# 05_RS232_USB.net
KiCad netlist of a schematic drawn in Altium Designer
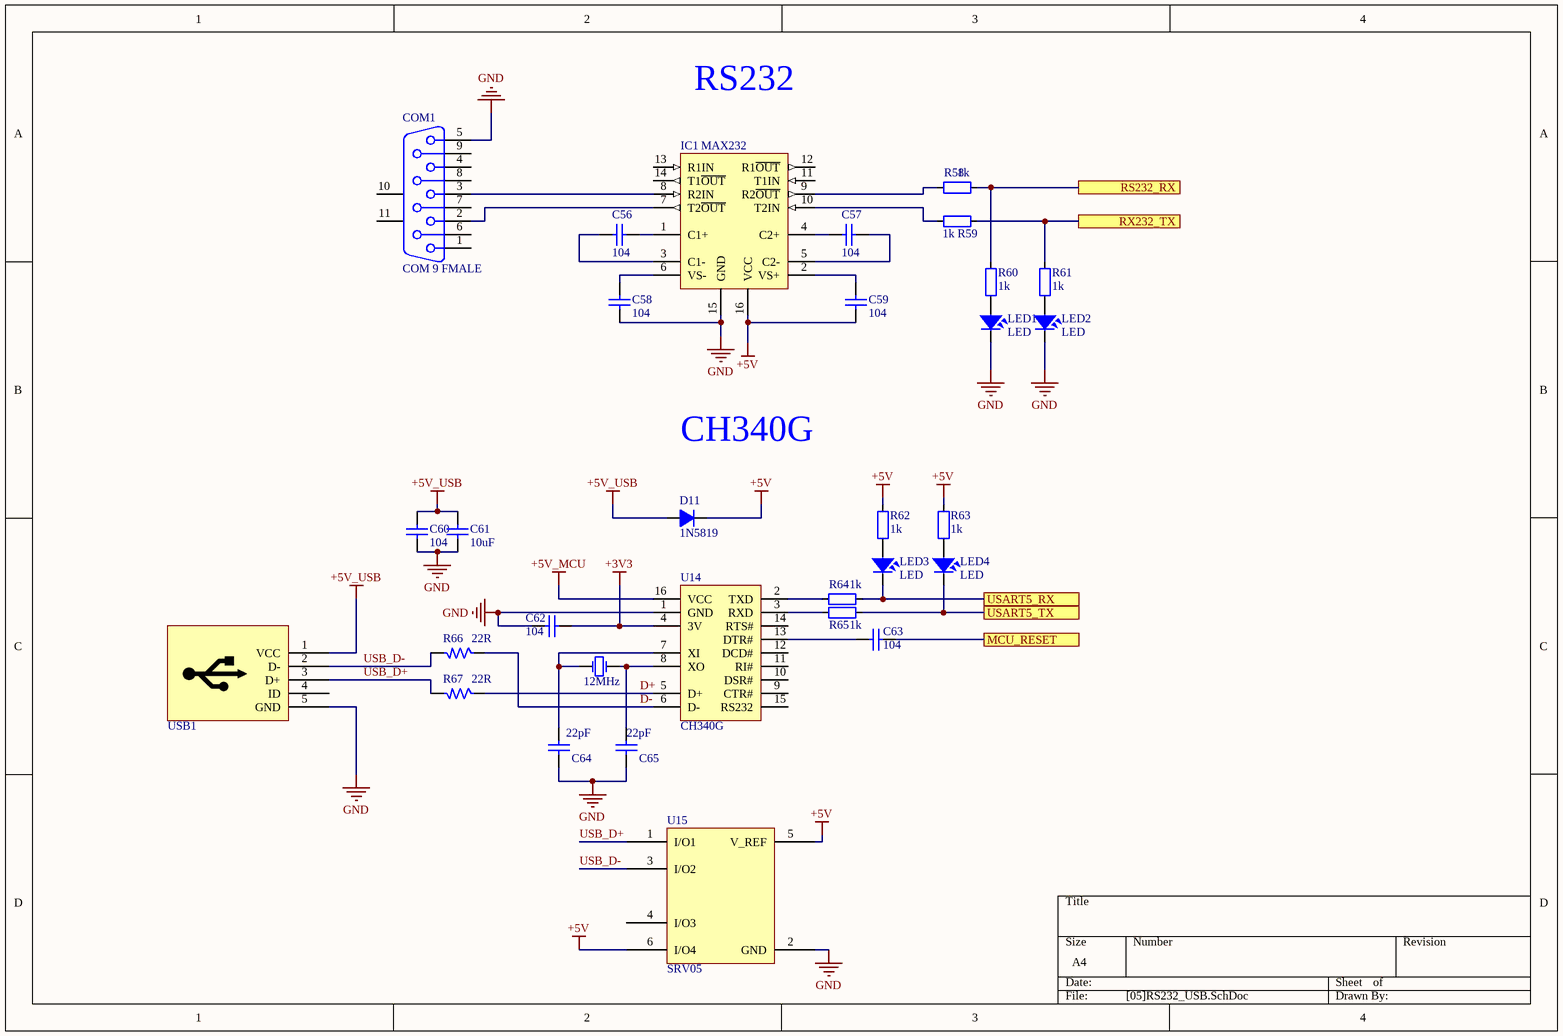
[diagram p0: [05]RS232_USB.SchDoc]

(export (version "E")
  (design (tool "Eeschema 10.0.6"))
  (components
    (comp (ref "C56")
      (value "104")
      (footprint "CAP_0603")
      (description "Capacitor")
      (fields (field (name "PUBLISHER") "Altium Limited"))
      (libsource (lib "My Library") (part "CapSMD"))
    )
    (comp (ref "C57")
      (value "104")
      (footprint "CAP_0603")
      (description "Capacitor")
      (fields (field (name "PUBLISHER") "Altium Limited"))
      (libsource (lib "My Library") (part "CapSMD"))
    )
    (comp (ref "C58")
      (value "104")
      (footprint "CAP_0603")
      (description "Capacitor")
      (fields (field (name "PUBLISHER") "Altium Limited"))
      (libsource (lib "My Library") (part "CapSMD"))
    )
    (comp (ref "C59")
      (value "104")
      (footprint "CAP_0603")
      (description "Capacitor")
      (fields (field (name "PUBLISHER") "Altium Limited"))
      (libsource (lib "My Library") (part "CapSMD"))
    )
    (comp (ref "C60")
      (value "104")
      (footprint "CAP_0603")
      (description "Capacitor")
      (fields (field (name "PUBLISHER") "Altium Limited"))
      (libsource (lib "My Library") (part "CapSMD"))
    )
    (comp (ref "C61")
      (value "10uF")
      (footprint "CAP_0603")
      (description "Capacitor")
      (fields (field (name "PUBLISHER") "Altium Limited"))
      (libsource (lib "My Library") (part "CapSMD"))
    )
    (comp (ref "C62")
      (value "104")
      (footprint "CAP_0603")
      (description "Capacitor")
      (fields (field (name "PUBLISHER") "Altium Limited"))
      (libsource (lib "My Library") (part "CapSMD"))
    )
    (comp (ref "C63")
      (value "104")
      (footprint "CAP_0603")
      (description "Capacitor")
      (fields (field (name "PUBLISHER") "Altium Limited"))
      (libsource (lib "My Library") (part "CapSMD"))
    )
    (comp (ref "C64")
      (value "22pF")
      (footprint "CAP_0603")
      (description "Capacitor")
      (fields (field (name "PUBLISHER") "Altium Limited"))
      (libsource (lib "My Library") (part "CapSMD"))
    )
    (comp (ref "C65")
      (value "22pF")
      (footprint "CAP_0603")
      (description "Capacitor")
      (fields (field (name "PUBLISHER") "Altium Limited"))
      (libsource (lib "My Library") (part "CapSMD"))
    )
    (comp (ref "COM1")
      (value "COM 9 FMALE")
      (footprint "DSB 9-F")
      (description "COM 9")
      (fields (field (name "PUBLISHER") "Altium Limited"))
      (libsource (lib "syhaunguyen") (part "DSB9F"))
    )
    (comp (ref "D11")
      (value "1N5819")
      (footprint "DO-214AB SMA")
      (description "Diode 1A")
      (libsource (lib "GPS_Traking_V1_1") (part "D1A_1"))
    )
    (comp (ref "IC1")
      (value "MAX232")
      (footprint "MAX232DR")
      (description "Dual EIA-232 Driver/Receiver")
      (libsource (lib "My Library") (part "MAX232"))
    )
    (comp (ref "LED1")
      (value "LED")
      (footprint "LED-0805-Green")
      (description "LED Single colour Green and Red")
      (libsource (lib "My Library") (part "LED"))
    )
    (comp (ref "LED2")
      (value "LED")
      (footprint "LED-0805-Green")
      (description "LED Single colour Green and Red")
      (libsource (lib "My Library") (part "LED"))
    )
    (comp (ref "LED3")
      (value "LED")
      (footprint "LED-0805-Green")
      (description "LED Single colour Green and Red")
      (libsource (lib "My Library") (part "LED"))
    )
    (comp (ref "LED4")
      (value "LED")
      (footprint "LED-0805-Green")
      (description "LED Single colour Green and Red")
      (libsource (lib "My Library") (part "LED"))
    )
    (comp (ref "R58")
      (value "1k")
      (footprint "RES-SMD-0603")
      (description "Resistor")
      (fields
        (field (name "MANUFACTURER") "Generic Components")
        (field (name "PUBLISHER") "Altium Hobart Technology Centre")
      )
      (libsource (lib "My Library") (part "Resistor - SMD"))
    )
    (comp (ref "R59")
      (value "1k")
      (footprint "RES-SMD-0603")
      (description "Resistor")
      (fields
        (field (name "MANUFACTURER") "Generic Components")
        (field (name "PUBLISHER") "Altium Hobart Technology Centre")
      )
      (libsource (lib "My Library") (part "Resistor - SMD"))
    )
    (comp (ref "R60")
      (value "1k")
      (footprint "RES-SMD-0603")
      (description "Resistor")
      (fields
        (field (name "MANUFACTURER") "Generic Components")
        (field (name "PUBLISHER") "Altium Hobart Technology Centre")
      )
      (libsource (lib "My Library") (part "Resistor - SMD"))
    )
    (comp (ref "R61")
      (value "1k")
      (footprint "RES-SMD-0603")
      (description "Resistor")
      (fields
        (field (name "MANUFACTURER") "Generic Components")
        (field (name "PUBLISHER") "Altium Hobart Technology Centre")
      )
      (libsource (lib "My Library") (part "Resistor - SMD"))
    )
    (comp (ref "R62")
      (value "1k")
      (footprint "RES-SMD-0603")
      (description "Resistor")
      (fields
        (field (name "MANUFACTURER") "Generic Components")
        (field (name "PUBLISHER") "Altium Hobart Technology Centre")
      )
      (libsource (lib "My Library") (part "Resistor - SMD"))
    )
    (comp (ref "R63")
      (value "1k")
      (footprint "RES-SMD-0603")
      (description "Resistor")
      (fields
        (field (name "MANUFACTURER") "Generic Components")
        (field (name "PUBLISHER") "Altium Hobart Technology Centre")
      )
      (libsource (lib "My Library") (part "Resistor - SMD"))
    )
    (comp (ref "R64")
      (value "1k")
      (footprint "RES-SMD-0603")
      (description "Resistor")
      (fields
        (field (name "MANUFACTURER") "Generic Components")
        (field (name "PUBLISHER") "Altium Hobart Technology Centre")
      )
      (libsource (lib "My Library") (part "Resistor - SMD"))
    )
    (comp (ref "R65")
      (value "1k")
      (footprint "RES-SMD-0603")
      (description "Resistor")
      (fields
        (field (name "MANUFACTURER") "Generic Components")
        (field (name "PUBLISHER") "Altium Hobart Technology Centre")
      )
      (libsource (lib "My Library") (part "Resistor - SMD"))
    )
    (comp (ref "R66")
      (value "22R")
      (footprint "RES-SMD-0603")
      (description "Resistor SMD")
      (libsource (lib "GPS_Traking_V1_1") (part "RM"))
    )
    (comp (ref "R67")
      (value "22R")
      (footprint "RES-SMD-0603")
      (description "Resistor SMD")
      (libsource (lib "GPS_Traking_V1_1") (part "RM"))
    )
    (comp (ref "U14")
      (value "CH340G")
      (footprint "SO16")
      (description "High and Low Side Driver")
      (fields (field (name "PUBLISHER") "Altium Limited"))
      (libsource (lib "My Library") (part "CH340G"))
    )
    (comp (ref "U15")
      (value "SRV05")
      (footprint "SOT23-6")
      (description "TVS DIODE 5V")
      (libsource (lib "My Library") (part "SRV05"))
    )
    (comp (ref "USB1") (value "USB") (footprint "USB-B-Mini") (libsource (lib "My Library") (part "USB-M")))
    (comp (ref "Y2")
      (value "12MHz")
      (footprint "XTAL-5032")
      (description "Crystal Oscillator")
      (fields (field (name "PUBLISHER") "Altium Limited"))
      (libsource (lib "My Library") (part "XTAL"))
    )
  )
  (nets
    (net (code "1") (name "+3V3") (class "Default")
      (node (ref "C62") (pin "2") (pinfunction "2_2") (pintype "passive"))
      (node (ref "U14") (pin "4") (pinfunction "3V_4") (pintype "passive"))
    )
    (net (code "2") (name "+5V") (class "Default")
      (node (ref "C59") (pin "2") (pinfunction "2_2") (pintype "passive"))
      (node (ref "D11") (pin "2") (pinfunction "K_2") (pintype "passive"))
      (node (ref "IC1") (pin "16") (pinfunction "VCC_16") (pintype "power_in"))
      (node (ref "R62") (pin "2") (pinfunction "2_2") (pintype "passive"))
      (node (ref "R63") (pin "2") (pinfunction "2_2") (pintype "passive"))
      (node (ref "U15") (pin "5") (pinfunction "V_REF_5") (pintype "passive"))
      (node (ref "U15") (pin "6") (pinfunction "I/O4_6") (pintype "passive"))
    )
    (net (code "3") (name "+5V_MCU") (class "Default")
      (node (ref "U14") (pin "16") (pinfunction "VCC_16") (pintype "passive"))
    )
    (net (code "4") (name "+5V_USB") (class "Default")
      (node (ref "C60") (pin "2") (pinfunction "2_2") (pintype "passive"))
      (node (ref "C61") (pin "2") (pinfunction "2_2") (pintype "passive"))
      (node (ref "D11") (pin "1") (pinfunction "A_1") (pintype "passive"))
      (node (ref "USB1") (pin "1") (pinfunction "VCC_1") (pintype "passive"))
    )
    (net (code "5") (name "/D+") (class "Default")
      (node (ref "R67") (pin "1") (pinfunction "1_1") (pintype "passive"))
      (node (ref "U14") (pin "5") (pinfunction "D+_5") (pintype "passive"))
    )
    (net (code "6") (name "/D-") (class "Default")
      (node (ref "R66") (pin "1") (pinfunction "1_1") (pintype "passive"))
      (node (ref "U14") (pin "6") (pinfunction "D-_6") (pintype "passive"))
    )
    (net (code "7") (name "/MCU_RESET") (class "Default")
      (node (ref "C63") (pin "2") (pinfunction "2_2") (pintype "passive"))
    )
    (net (code "8") (name "/RS232_RX") (class "Default")
      (node (ref "R58") (pin "1") (pinfunction "1_1") (pintype "passive"))
      (node (ref "R60") (pin "2") (pinfunction "2_2") (pintype "passive"))
    )
    (net (code "9") (name "/RX232_TX") (class "Default")
      (node (ref "R59") (pin "1") (pinfunction "1_1") (pintype "passive"))
      (node (ref "R61") (pin "2") (pinfunction "2_2") (pintype "passive"))
    )
    (net (code "10") (name "/USART5_RX") (class "Default")
      (node (ref "LED3") (pin "2") (pinfunction "2_2") (pintype "passive"))
      (node (ref "R64") (pin "2") (pinfunction "2_2") (pintype "passive"))
    )
    (net (code "11") (name "/USART5_TX") (class "Default")
      (node (ref "LED4") (pin "2") (pinfunction "2_2") (pintype "passive"))
      (node (ref "R65") (pin "2") (pinfunction "2_2") (pintype "passive"))
    )
    (net (code "12") (name "/USB_D+") (class "Default")
      (node (ref "R67") (pin "2") (pinfunction "2_2") (pintype "passive"))
      (node (ref "U15") (pin "1") (pinfunction "I/O1_1") (pintype "passive"))
      (node (ref "USB1") (pin "3") (pinfunction "D+_3") (pintype "passive"))
    )
    (net (code "13") (name "/USB_D-") (class "Default")
      (node (ref "R66") (pin "2") (pinfunction "2_2") (pintype "passive"))
      (node (ref "U15") (pin "3") (pinfunction "I/O2_3") (pintype "passive"))
      (node (ref "USB1") (pin "2") (pinfunction "D-_2") (pintype "passive"))
    )
    (net (code "14") (name "GND") (class "Default")
      (node (ref "C58") (pin "2") (pinfunction "2_2") (pintype "passive"))
      (node (ref "C60") (pin "1") (pinfunction "1_1") (pintype "passive"))
      (node (ref "C61") (pin "1") (pinfunction "1_1") (pintype "passive"))
      (node (ref "C62") (pin "1") (pinfunction "1_1") (pintype "passive"))
      (node (ref "C64") (pin "2") (pinfunction "2_2") (pintype "passive"))
      (node (ref "C65") (pin "2") (pinfunction "2_2") (pintype "passive"))
      (node (ref "COM1") (pin "5") (pinfunction "5_5") (pintype "passive"))
      (node (ref "IC1") (pin "15") (pinfunction "GND_15") (pintype "power_in"))
      (node (ref "LED1") (pin "2") (pinfunction "2_2") (pintype "passive"))
      (node (ref "LED2") (pin "2") (pinfunction "2_2") (pintype "passive"))
      (node (ref "U14") (pin "1") (pinfunction "GND_1") (pintype "passive"))
      (node (ref "U15") (pin "2") (pinfunction "GND_2") (pintype "passive"))
      (node (ref "USB1") (pin "5") (pinfunction "GND_5") (pintype "passive"))
    )
    (net (code "15") (name "Net-(IC1-C1+)") (class "Default")
      (node (ref "C56") (pin "1") (pinfunction "1_1") (pintype "passive"))
      (node (ref "IC1") (pin "1") (pinfunction "C1+_1") (pintype "passive"))
    )
    (net (code "16") (name "Net-(IC1-C1-)") (class "Default")
      (node (ref "C56") (pin "2") (pinfunction "2_2") (pintype "passive"))
      (node (ref "IC1") (pin "3") (pinfunction "C1-_3") (pintype "passive"))
    )
    (net (code "17") (name "Net-(IC1-C2+)") (class "Default")
      (node (ref "C57") (pin "2") (pinfunction "2_2") (pintype "passive"))
      (node (ref "IC1") (pin "4") (pinfunction "C2+_4") (pintype "passive"))
    )
    (net (code "18") (name "Net-(IC1-C2-)") (class "Default")
      (node (ref "C57") (pin "1") (pinfunction "1_1") (pintype "passive"))
      (node (ref "IC1") (pin "5") (pinfunction "C2-_5") (pintype "passive"))
    )
    (net (code "19") (name "Net-(IC1-R2IN)") (class "Default")
      (node (ref "COM1") (pin "3") (pinfunction "3_3") (pintype "passive"))
      (node (ref "IC1") (pin "8") (pinfunction "R2IN_8") (pintype "input"))
    )
    (net (code "20") (name "Net-(IC1-R2~{OUT})") (class "Default")
      (node (ref "IC1") (pin "9") (pinfunction "R2~{OUT}_9") (pintype "output"))
      (node (ref "R58") (pin "2") (pinfunction "2_2") (pintype "passive"))
    )
    (net (code "21") (name "Net-(IC1-T2IN)") (class "Default")
      (node (ref "IC1") (pin "10") (pinfunction "T2IN_10") (pintype "input"))
      (node (ref "R59") (pin "2") (pinfunction "2_2") (pintype "passive"))
    )
    (net (code "22") (name "Net-(IC1-T2~{OUT})") (class "Default")
      (node (ref "COM1") (pin "2") (pinfunction "2_2") (pintype "passive"))
      (node (ref "IC1") (pin "7") (pinfunction "T2~{OUT}_7") (pintype "output"))
    )
    (net (code "23") (name "Net-(IC1-VS+)") (class "Default")
      (node (ref "C59") (pin "1") (pinfunction "1_1") (pintype "passive"))
      (node (ref "IC1") (pin "2") (pinfunction "VS+_2") (pintype "power_in"))
    )
    (net (code "24") (name "Net-(IC1-VS-)") (class "Default")
      (node (ref "C58") (pin "1") (pinfunction "1_1") (pintype "passive"))
      (node (ref "IC1") (pin "6") (pinfunction "VS-_6") (pintype "power_in"))
    )
    (net (code "25") (name "Net-(LED1-Pad1)") (class "Default")
      (node (ref "LED1") (pin "1") (pinfunction "1_1") (pintype "passive"))
      (node (ref "R60") (pin "1") (pinfunction "1_1") (pintype "passive"))
    )
    (net (code "26") (name "Net-(LED2-Pad1)") (class "Default")
      (node (ref "LED2") (pin "1") (pinfunction "1_1") (pintype "passive"))
      (node (ref "R61") (pin "1") (pinfunction "1_1") (pintype "passive"))
    )
    (net (code "27") (name "Net-(LED3-Pad1)") (class "Default")
      (node (ref "LED3") (pin "1") (pinfunction "1_1") (pintype "passive"))
      (node (ref "R62") (pin "1") (pinfunction "1_1") (pintype "passive"))
    )
    (net (code "28") (name "Net-(LED4-Pad1)") (class "Default")
      (node (ref "LED4") (pin "1") (pinfunction "1_1") (pintype "passive"))
      (node (ref "R63") (pin "1") (pinfunction "1_1") (pintype "passive"))
    )
    (net (code "29") (name "Net-(U14-DTR#)") (class "Default")
      (node (ref "C63") (pin "1") (pinfunction "1_1") (pintype "passive"))
      (node (ref "U14") (pin "13") (pinfunction "DTR#_13") (pintype "passive"))
    )
    (net (code "30") (name "Net-(U14-RXD)") (class "Default")
      (node (ref "R65") (pin "1") (pinfunction "1_1") (pintype "passive"))
      (node (ref "U14") (pin "3") (pinfunction "RXD_3") (pintype "passive"))
    )
    (net (code "31") (name "Net-(U14-TXD)") (class "Default")
      (node (ref "R64") (pin "1") (pinfunction "1_1") (pintype "passive"))
      (node (ref "U14") (pin "2") (pinfunction "TXD_2") (pintype "passive"))
    )
    (net (code "32") (name "Net-(U14-XI)") (class "Default")
      (node (ref "C64") (pin "1") (pinfunction "1_1") (pintype "passive"))
      (node (ref "U14") (pin "7") (pinfunction "XI_7") (pintype "passive"))
      (node (ref "Y2") (pin "1") (pinfunction "OSC1_1") (pintype "passive"))
    )
    (net (code "33") (name "Net-(U14-XO)") (class "Default")
      (node (ref "C65") (pin "1") (pinfunction "1_1") (pintype "passive"))
      (node (ref "U14") (pin "8") (pinfunction "XO_8") (pintype "passive"))
      (node (ref "Y2") (pin "2") (pinfunction "OSC2_2") (pintype "passive"))
    )
    (net (code "34") (name "unconnected-(COM1-MH1-Pad10)") (class "Default")
      (node (ref "COM1") (pin "10") (pinfunction "MH1_10") (pintype "passive"))
    )
    (net (code "35") (name "unconnected-(COM1-MH2-Pad11)") (class "Default")
      (node (ref "COM1") (pin "11") (pinfunction "MH2_11") (pintype "passive"))
    )
    (net (code "36") (name "unconnected-(COM1-Pad1)") (class "Default")
      (node (ref "COM1") (pin "1") (pinfunction "1_1") (pintype "passive"))
    )
    (net (code "37") (name "unconnected-(COM1-Pad4)") (class "Default")
      (node (ref "COM1") (pin "4") (pinfunction "4_4") (pintype "passive"))
    )
    (net (code "38") (name "unconnected-(COM1-Pad6)") (class "Default")
      (node (ref "COM1") (pin "6") (pinfunction "6_6") (pintype "passive"))
    )
    (net (code "39") (name "unconnected-(COM1-Pad7)") (class "Default")
      (node (ref "COM1") (pin "7") (pinfunction "7_7") (pintype "passive"))
    )
    (net (code "40") (name "unconnected-(COM1-Pad8)") (class "Default")
      (node (ref "COM1") (pin "8") (pinfunction "8_8") (pintype "passive"))
    )
    (net (code "41") (name "unconnected-(COM1-Pad9)") (class "Default")
      (node (ref "COM1") (pin "9") (pinfunction "9_9") (pintype "passive"))
    )
    (net (code "42") (name "unconnected-(IC1-R1IN-Pad13)") (class "Default")
      (node (ref "IC1") (pin "13") (pinfunction "R1IN_13") (pintype "input"))
    )
    (net (code "43") (name "unconnected-(IC1-R1~{OUT}-Pad12)") (class "Default")
      (node (ref "IC1") (pin "12") (pinfunction "R1~{OUT}_12") (pintype "output"))
    )
    (net (code "44") (name "unconnected-(IC1-T1IN-Pad11)") (class "Default")
      (node (ref "IC1") (pin "11") (pinfunction "T1IN_11") (pintype "input"))
    )
    (net (code "45") (name "unconnected-(IC1-T1~{OUT}-Pad14)") (class "Default")
      (node (ref "IC1") (pin "14") (pinfunction "T1~{OUT}_14") (pintype "output"))
    )
    (net (code "46") (name "unconnected-(U14-CTR#-Pad9)") (class "Default")
      (node (ref "U14") (pin "9") (pinfunction "CTR#_9") (pintype "passive"))
    )
    (net (code "47") (name "unconnected-(U14-DCD#-Pad12)") (class "Default")
      (node (ref "U14") (pin "12") (pinfunction "DCD#_12") (pintype "passive"))
    )
    (net (code "48") (name "unconnected-(U14-DSR#-Pad10)") (class "Default")
      (node (ref "U14") (pin "10") (pinfunction "DSR#_10") (pintype "passive"))
    )
    (net (code "49") (name "unconnected-(U14-RI#-Pad11)") (class "Default")
      (node (ref "U14") (pin "11") (pinfunction "RI#_11") (pintype "passive"))
    )
    (net (code "50") (name "unconnected-(U14-RS232-Pad15)") (class "Default")
      (node (ref "U14") (pin "15") (pinfunction "RS232_15") (pintype "passive"))
    )
    (net (code "51") (name "unconnected-(U14-RTS#-Pad14)") (class "Default")
      (node (ref "U14") (pin "14") (pinfunction "RTS#_14") (pintype "passive"))
    )
    (net (code "52") (name "unconnected-(U15-I{slash}O3-Pad4)") (class "Default")
      (node (ref "U15") (pin "4") (pinfunction "I/O3_4") (pintype "passive"))
    )
    (net (code "53") (name "unconnected-(USB1-ID-Pad4)") (class "Default")
      (node (ref "USB1") (pin "4") (pinfunction "ID_4") (pintype "passive"))
    )
  )
)
